# design.net
KiCad netlist of a schematic drawn in Altium Designer
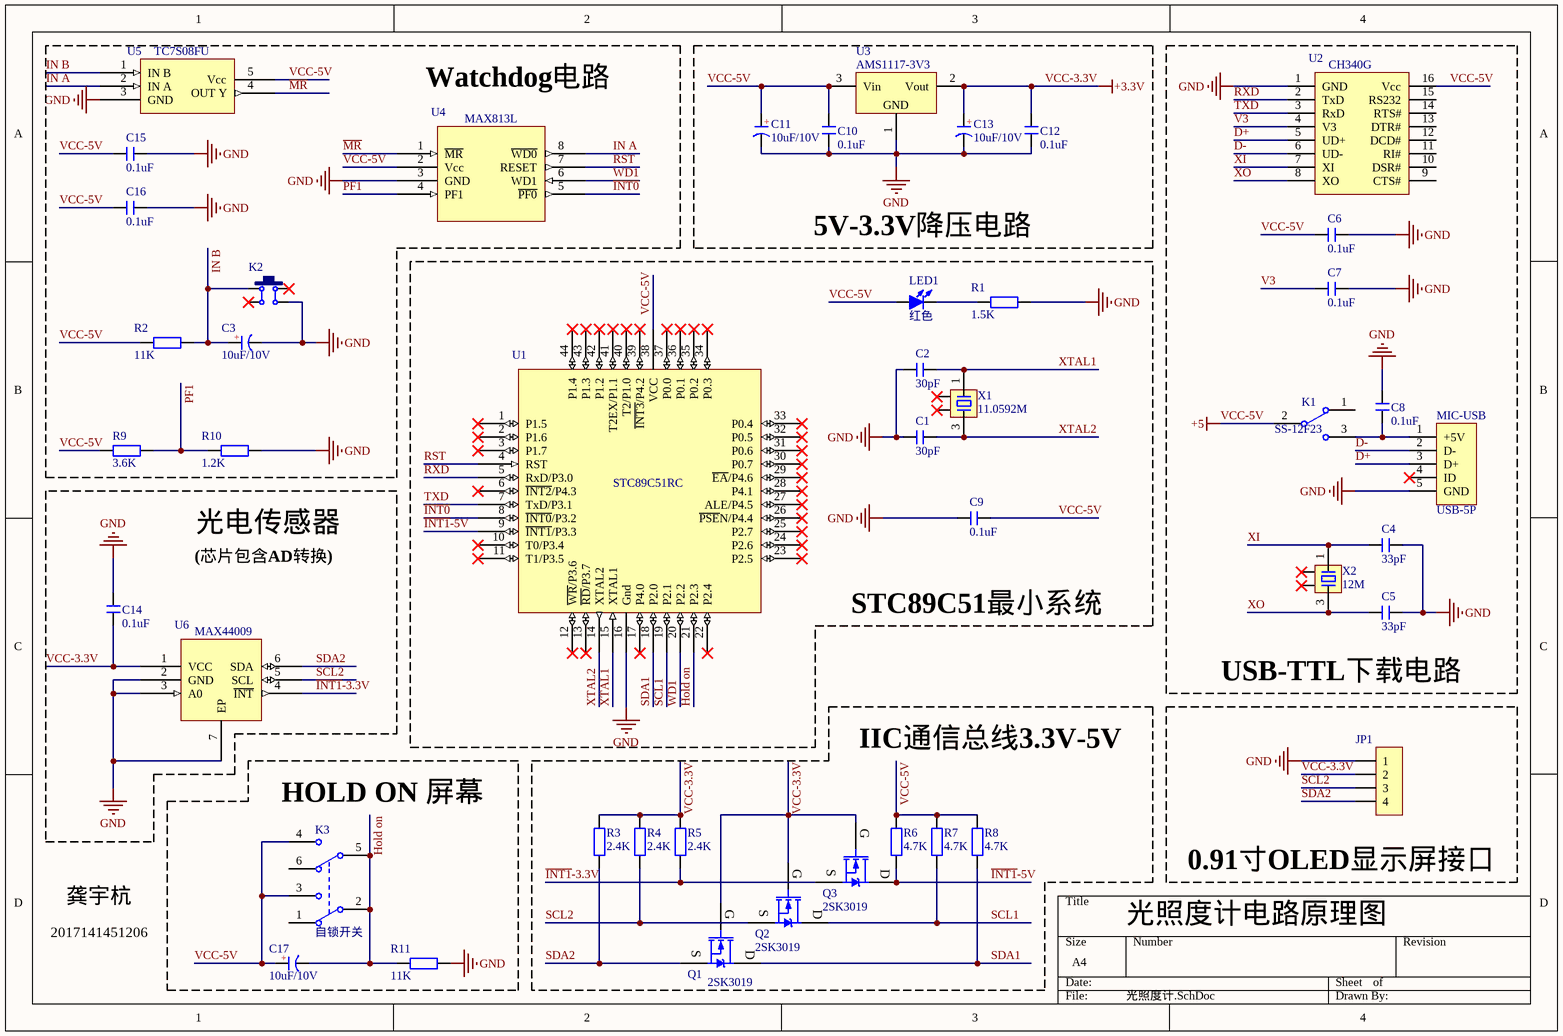
[diagram p0: 光照度计.SchDoc]

(export (version "E")
  (design (tool "Eeschema 10.0.6"))
  (components
    (comp (ref "C1")
      (value "30pF")
      (footprint "C 0805_L")
      (description "贴片电容")
      (libsource (lib "*") (part "C"))
    )
    (comp (ref "C2")
      (value "30pF")
      (footprint "C 0805_L")
      (description "贴片电容")
      (libsource (lib "*") (part "C"))
    )
    (comp (ref "C3")
      (value "10uF/10V")
      (footprint "CM A(3*5.4)")
      (description "贴片电解电容")
      (fields (field (name "版权归属") "封装库来自淘宝 ID：黄晶宝石"))
      (libsource (lib "") (part "CE_SMD_1"))
    )
    (comp (ref "C4")
      (value "33pF")
      (footprint "C 0805_L")
      (description "贴片电容")
      (libsource (lib "*") (part "C"))
    )
    (comp (ref "C5")
      (value "33pF")
      (footprint "C 0805_L")
      (description "贴片电容")
      (libsource (lib "*") (part "C"))
    )
    (comp (ref "C6")
      (value "0.1uF")
      (footprint "C 0805_L")
      (description "贴片电容")
      (libsource (lib "*") (part "C"))
    )
    (comp (ref "C7")
      (value "0.1uF")
      (footprint "C 0805_L")
      (description "贴片电容")
      (libsource (lib "*") (part "C"))
    )
    (comp (ref "C8")
      (value "0.1uF")
      (footprint "C 0805_L")
      (description "贴片电容")
      (libsource (lib "*") (part "C"))
    )
    (comp (ref "C9")
      (value "0.1uF")
      (footprint "C 0805_L")
      (description "贴片电容")
      (libsource (lib "*") (part "C"))
    )
    (comp (ref "C10")
      (value "0.1uF")
      (footprint "C 0805_L")
      (description "贴片电容")
      (libsource (lib "*") (part "C"))
    )
    (comp (ref "C11")
      (value "10uF/10V")
      (footprint "CM A(3*5.4)")
      (description "贴片电解电容")
      (fields (field (name "版权归属") "封装库来自淘宝 ID：黄晶宝石"))
      (libsource (lib "*") (part "CE_SMD"))
    )
    (comp (ref "C12")
      (value "0.1uF")
      (footprint "C 0805_L")
      (description "贴片电容")
      (libsource (lib "*") (part "C"))
    )
    (comp (ref "C13")
      (value "10uF/10V")
      (footprint "CM A(3*5.4)")
      (description "贴片电解电容")
      (fields (field (name "版权归属") "封装库来自淘宝 ID：黄晶宝石"))
      (libsource (lib "*") (part "CE_SMD"))
    )
    (comp (ref "C14")
      (value "0.1uF")
      (footprint "C 0805_L")
      (description "贴片电容")
      (libsource (lib "*") (part "C"))
    )
    (comp (ref "C15")
      (value "0.1uF")
      (footprint "C 0805_L")
      (description "贴片电容")
      (libsource (lib "*") (part "C"))
    )
    (comp (ref "C16")
      (value "0.1uF")
      (footprint "C 0805_L")
      (description "贴片电容")
      (libsource (lib "*") (part "C"))
    )
    (comp (ref "C17")
      (value "10uF/10V")
      (footprint "CM A(3*5.4)")
      (description "贴片电解电容")
      (fields (field (name "版权归属") "封装库来自淘宝 ID：黄晶宝石"))
      (libsource (lib "") (part "CE_SMD_1"))
    )
    (comp (ref "JP1")
      (value "HDR-1X4")
      (footprint "HDR2.54-M-LI-4P")
      (description "4P接插件")
      (fields (field (name "版权归属") "封装库来自淘宝 ID：黄晶宝石"))
      (libsource (lib "*") (part "Header 4"))
    )
    (comp (ref "K1")
      (value "SS-12F23")
      (footprint "MSK-12C01-07")
      (description "1路波动开关")
      (fields (field (name "版权归属") "封装库来自淘宝 ID：黄晶宝石"))
      (libsource (lib "*") (part "SSW-1P"))
    )
    (comp (ref "K2")
      (value "6x6x5")
      (footprint "TSW SMD-6*6*4.3")
      (description "贴片6x6轻触开关")
      (fields (field (name "版权归属") "封装库来自淘宝 ID：黄晶宝石"))
      (libsource (lib "*") (part "TSW SMD-6x6"))
    )
    (comp (ref "K3")
      (value "自锁开关")
      (footprint "KFT DIP-7X7")
      (description "7*7自锁开关")
      (fields (field (name "版权归属") "封装库来自淘宝 ID：黄晶宝石"))
      (libsource (lib "*") (part "KET 7X7"))
    )
    (comp (ref "LED1")
      (value "红色")
      (footprint "LED 0805G")
      (description "贴片LED")
      (fields (field (name "版权归属") "封装库来自淘宝 ID：黄晶宝石"))
      (libsource (lib "*") (part "LED-SMD"))
    )
    (comp (ref "MIC-USB")
      (value "USB-5P")
      (footprint "USB-MICRO_A")
      (description "微型USB母座")
      (libsource (lib "*") (part "USB-5P"))
    )
    (comp (ref "Q1")
      (value "2SK3019")
      (footprint "SOT523")
      (description "N沟场效应管")
      (libsource (lib "*") (part "2SK3019"))
    )
    (comp (ref "Q2")
      (value "2SK3019")
      (footprint "SOT523")
      (description "N沟场效应管")
      (libsource (lib "*") (part "2SK3019"))
    )
    (comp (ref "Q3")
      (value "2SK3019")
      (footprint "SOT523")
      (description "N沟场效应管")
      (libsource (lib "*") (part "2SK3019"))
    )
    (comp (ref "R1")
      (value "1.5K")
      (footprint "R 0805_L")
      (description "贴片电阻")
      (fields (field (name "版权归属") "来自淘宝 ID：黄晶宝石"))
      (libsource (lib "*") (part "R"))
    )
    (comp (ref "R2")
      (value "11K")
      (footprint "R 0805_L")
      (description "贴片电阻")
      (fields (field (name "版权归属") "来自淘宝 ID：黄晶宝石"))
      (libsource (lib "*") (part "R"))
    )
    (comp (ref "R3")
      (value "2.4K")
      (footprint "R 0805_L")
      (description "贴片电阻")
      (fields (field (name "版权归属") "来自淘宝 ID：黄晶宝石"))
      (libsource (lib "*") (part "R"))
    )
    (comp (ref "R4")
      (value "2.4K")
      (footprint "R 0805_L")
      (description "贴片电阻")
      (fields (field (name "版权归属") "来自淘宝 ID：黄晶宝石"))
      (libsource (lib "*") (part "R"))
    )
    (comp (ref "R5")
      (value "2.4K")
      (footprint "R 0805_L")
      (description "贴片电阻")
      (fields (field (name "版权归属") "来自淘宝 ID：黄晶宝石"))
      (libsource (lib "*") (part "R"))
    )
    (comp (ref "R6")
      (value "4.7K")
      (footprint "R 0805_L")
      (description "贴片电阻")
      (fields (field (name "版权归属") "来自淘宝 ID：黄晶宝石"))
      (libsource (lib "*") (part "R"))
    )
    (comp (ref "R7")
      (value "4.7K")
      (footprint "R 0805_L")
      (description "贴片电阻")
      (fields (field (name "版权归属") "来自淘宝 ID：黄晶宝石"))
      (libsource (lib "*") (part "R"))
    )
    (comp (ref "R8")
      (value "4.7K")
      (footprint "R 0805_L")
      (description "贴片电阻")
      (fields (field (name "版权归属") "来自淘宝 ID：黄晶宝石"))
      (libsource (lib "*") (part "R"))
    )
    (comp (ref "R9")
      (value "3.6K")
      (footprint "R 0805_L")
      (description "贴片电阻")
      (fields (field (name "版权归属") "来自淘宝 ID：黄晶宝石"))
      (libsource (lib "*") (part "R"))
    )
    (comp (ref "R10")
      (value "1.2K")
      (footprint "R 0805_L")
      (description "贴片电阻")
      (fields (field (name "版权归属") "来自淘宝 ID：黄晶宝石"))
      (libsource (lib "*") (part "R"))
    )
    (comp (ref "R11")
      (value "11K")
      (footprint "R 0805_L")
      (description "贴片电阻")
      (fields (field (name "版权归属") "来自淘宝 ID：黄晶宝石"))
      (libsource (lib "*") (part "R"))
    )
    (comp (ref "U1")
      (value "STC89C51RC")
      (footprint "LQFP44 10X10_N")
      (description "STC单片机贴片")
      (libsource (lib "*") (part "STC89C51RC-44pin"))
    )
    (comp (ref "U2")
      (value "CH340G")
      (footprint "SOP16_N")
      (description "串口转USB")
      (fields (field (name "版权归属") "封装库来自淘宝 ID：黄晶宝石"))
      (libsource (lib "*") (part "CH340G"))
    )
    (comp (ref "U3")
      (value "AMS1117-3V3")
      (footprint "SOT223_N")
      (description "三端稳压芯片")
      (libsource (lib "02模块IC器件库") (part "AMS1117"))
    )
    (comp (ref "U4")
      (value "MAX813L")
      (footprint "SOP8-N-MAX813L")
      (description "电源监控芯片（看门狗）")
      (libsource (lib "*") (part "MAX813L"))
    )
    (comp (ref "U5")
      (value "TC7S08FU")
      (footprint "TSOP65P210X100-5M")
      (description "2输入与门（一个）")
      (libsource (lib "*") (part "TC7S08FU-2输入与门"))
    )
    (comp (ref "U6")
      (value "MAX44009")
      (footprint "QFN65P200X200X65_HS-7N")
      (description "光照度传感器")
      (libsource (lib "*") (part "MAX44009"))
    )
    (comp (ref "X1")
      (value "11.0592M")
      (footprint "OSC 3225-4P")
      (description "4脚无源晶振")
      (fields (field (name "版权归属") "封装库来自淘宝卖家 ID：黄晶宝石"))
      (libsource (lib "*") (part "XTAL-4P"))
    )
    (comp (ref "X2")
      (value "12M")
      (footprint "OSC 3225-4P")
      (description "4脚无源晶振")
      (fields (field (name "版权归属") "封装库来自淘宝卖家 ID：黄晶宝石"))
      (libsource (lib "*") (part "XTAL-4P"))
    )
  )
  (nets
    (net (code "1") (name "+3.3V") (class "Default")
      (node (ref "C12") (pin "2") (pinfunction "2_2") (pintype "passive"))
      (node (ref "C13") (pin "1") (pinfunction "A_1") (pintype "passive"))
      (node (ref "C14") (pin "2") (pinfunction "2_2") (pintype "passive"))
      (node (ref "JP1") (pin "2") (pinfunction "2_2") (pintype "passive"))
      (node (ref "Q1") (pin "1") (pinfunction "G_1") (pintype "passive"))
      (node (ref "Q2") (pin "1") (pinfunction "G_1") (pintype "passive"))
      (node (ref "Q3") (pin "1") (pinfunction "G_1") (pintype "passive"))
      (node (ref "R3") (pin "2") (pinfunction "2_2") (pintype "passive"))
      (node (ref "R4") (pin "2") (pinfunction "2_2") (pintype "passive"))
      (node (ref "R5") (pin "2") (pinfunction "2_2") (pintype "passive"))
      (node (ref "U3") (pin "2") (pinfunction "Vout_2") (pintype "passive"))
      (node (ref "U6") (pin "1") (pinfunction "VCC_1") (pintype "power_in"))
    )
    (net (code "2") (name "+5") (class "Default")
      (node (ref "C10") (pin "2") (pinfunction "2_2") (pintype "passive"))
      (node (ref "C11") (pin "1") (pinfunction "A_1") (pintype "passive"))
      (node (ref "C15") (pin "2") (pinfunction "2_2") (pintype "passive"))
      (node (ref "C16") (pin "2") (pinfunction "2_2") (pintype "passive"))
      (node (ref "C17") (pin "1") (pinfunction "A_1") (pintype "passive"))
      (node (ref "C6") (pin "2") (pinfunction "2_2") (pintype "passive"))
      (node (ref "C9") (pin "2") (pinfunction "2_2") (pintype "passive"))
      (node (ref "K1") (pin "2") (pinfunction "2_2") (pintype "passive"))
      (node (ref "K3") (pin "3") (pinfunction "NO1_3") (pintype "passive"))
      (node (ref "K3") (pin "4") (pinfunction "NO2_4") (pintype "passive"))
      (node (ref "LED1") (pin "1") (pinfunction "A_1") (pintype "passive"))
      (node (ref "R2") (pin "1") (pinfunction "1_1") (pintype "passive"))
      (node (ref "R6") (pin "2") (pinfunction "2_2") (pintype "passive"))
      (node (ref "R7") (pin "2") (pinfunction "2_2") (pintype "passive"))
      (node (ref "R8") (pin "2") (pinfunction "2_2") (pintype "passive"))
      (node (ref "R9") (pin "2") (pinfunction "2_2") (pintype "passive"))
      (node (ref "U1") (pin "38") (pinfunction "VCC_38") (pintype "power_in"))
      (node (ref "U2") (pin "16") (pinfunction "Vcc_16") (pintype "passive"))
      (node (ref "U3") (pin "3") (pinfunction "Vin_3") (pintype "passive"))
      (node (ref "U4") (pin "2") (pinfunction "Vcc_2") (pintype "power_in"))
      (node (ref "U5") (pin "5") (pinfunction "Vcc_5") (pintype "power_in"))
    )
    (net (code "3") (name "/D+") (class "Default")
      (node (ref "MIC-USB") (pin "3") (pinfunction "D+_3") (pintype "passive"))
      (node (ref "U2") (pin "5") (pinfunction "UD+_5") (pintype "passive"))
    )
    (net (code "4") (name "/D-") (class "Default")
      (node (ref "MIC-USB") (pin "2") (pinfunction "D-_2") (pintype "passive"))
      (node (ref "U2") (pin "6") (pinfunction "UD-_6") (pintype "passive"))
    )
    (net (code "5") (name "/Hold on") (class "Default")
      (node (ref "C17") (pin "2") (pinfunction "K_2") (pintype "passive"))
      (node (ref "K3") (pin "2") (pinfunction "COM2_2") (pintype "passive"))
      (node (ref "K3") (pin "5") (pinfunction "COM2_5") (pintype "passive"))
      (node (ref "R11") (pin "1") (pinfunction "1_1") (pintype "passive"))
      (node (ref "U1") (pin "21") (pinfunction "P2.3_21") (pintype "bidirectional"))
    )
    (net (code "6") (name "/IN A") (class "Default")
      (node (ref "U4") (pin "8") (pinfunction "~{WD0}_8") (pintype "output"))
      (node (ref "U5") (pin "2") (pinfunction "IN_A_2") (pintype "input"))
    )
    (net (code "7") (name "/IN B") (class "Default")
      (node (ref "C3") (pin "1") (pinfunction "A_1") (pintype "passive"))
      (node (ref "K2") (pin "1") (pinfunction "1_1") (pintype "passive"))
      (node (ref "R2") (pin "2") (pinfunction "2_2") (pintype "passive"))
      (node (ref "U5") (pin "1") (pinfunction "IN_B_1") (pintype "input"))
    )
    (net (code "8") (name "/PF1") (class "Default")
      (node (ref "R10") (pin "1") (pinfunction "1_1") (pintype "passive"))
      (node (ref "R9") (pin "1") (pinfunction "1_1") (pintype "passive"))
      (node (ref "U4") (pin "4") (pinfunction "PF1_4") (pintype "input"))
    )
    (net (code "9") (name "/RST") (class "Default")
      (node (ref "U1") (pin "4") (pinfunction "RST_4") (pintype "input"))
      (node (ref "U4") (pin "7") (pinfunction "RESET_7") (pintype "output"))
    )
    (net (code "10") (name "/RXD") (class "Default")
      (node (ref "U1") (pin "5") (pinfunction "RxD/P3.0_5") (pintype "bidirectional"))
      (node (ref "U2") (pin "2") (pinfunction "TxD_2") (pintype "passive"))
    )
    (net (code "11") (name "/SCL1") (class "Default")
      (node (ref "Q2") (pin "2") (pinfunction "D_2") (pintype "passive"))
      (node (ref "R7") (pin "1") (pinfunction "1_1") (pintype "passive"))
      (node (ref "U1") (pin "19") (pinfunction "P2.1_19") (pintype "bidirectional"))
    )
    (net (code "12") (name "/SCL2") (class "Default")
      (node (ref "JP1") (pin "3") (pinfunction "3_3") (pintype "passive"))
      (node (ref "Q2") (pin "3") (pinfunction "S_3") (pintype "passive"))
      (node (ref "R4") (pin "1") (pinfunction "1_1") (pintype "passive"))
      (node (ref "U6") (pin "5") (pinfunction "SCL_5") (pintype "bidirectional"))
    )
    (net (code "13") (name "/SDA1") (class "Default")
      (node (ref "Q1") (pin "2") (pinfunction "D_2") (pintype "passive"))
      (node (ref "R8") (pin "1") (pinfunction "1_1") (pintype "passive"))
      (node (ref "U1") (pin "18") (pinfunction "P2.0_18") (pintype "bidirectional"))
    )
    (net (code "14") (name "/SDA2") (class "Default")
      (node (ref "JP1") (pin "4") (pinfunction "4_4") (pintype "passive"))
      (node (ref "Q1") (pin "3") (pinfunction "S_3") (pintype "passive"))
      (node (ref "R3") (pin "1") (pinfunction "1_1") (pintype "passive"))
      (node (ref "U6") (pin "6") (pinfunction "SDA_6") (pintype "bidirectional"))
    )
    (net (code "15") (name "/TXD") (class "Default")
      (node (ref "U1") (pin "7") (pinfunction "TxD/P3.1_7") (pintype "bidirectional"))
      (node (ref "U2") (pin "3") (pinfunction "RxD_3") (pintype "passive"))
    )
    (net (code "16") (name "/V3") (class "Default")
      (node (ref "C7") (pin "2") (pinfunction "2_2") (pintype "passive"))
      (node (ref "U2") (pin "4") (pinfunction "V3_4") (pintype "passive"))
    )
    (net (code "17") (name "/WD1") (class "Default")
      (node (ref "U1") (pin "20") (pinfunction "P2.2_20") (pintype "bidirectional"))
      (node (ref "U4") (pin "6") (pinfunction "WD1_6") (pintype "input"))
    )
    (net (code "18") (name "/XI") (class "Default")
      (node (ref "C4") (pin "2") (pinfunction "2_2") (pintype "passive"))
      (node (ref "U2") (pin "7") (pinfunction "XI_7") (pintype "passive"))
      (node (ref "X2") (pin "1") (pinfunction "1_1") (pintype "passive"))
    )
    (net (code "19") (name "/XO") (class "Default")
      (node (ref "C5") (pin "2") (pinfunction "2_2") (pintype "passive"))
      (node (ref "U2") (pin "8") (pinfunction "XO_8") (pintype "passive"))
      (node (ref "X2") (pin "3") (pinfunction "3_3") (pintype "passive"))
    )
    (net (code "20") (name "/XTAL1") (class "Default")
      (node (ref "C2") (pin "1") (pinfunction "1_1") (pintype "passive"))
      (node (ref "U1") (pin "15") (pinfunction "XTAL1_15") (pintype "input"))
      (node (ref "X1") (pin "1") (pinfunction "1_1") (pintype "passive"))
    )
    (net (code "21") (name "/XTAL2") (class "Default")
      (node (ref "C1") (pin "2") (pinfunction "2_2") (pintype "passive"))
      (node (ref "U1") (pin "14") (pinfunction "XTAL2_14") (pintype "output"))
      (node (ref "X1") (pin "3") (pinfunction "3_3") (pintype "passive"))
    )
    (net (code "22") (name "/~{INT0}") (class "Default")
      (node (ref "U1") (pin "8") (pinfunction "~{INT0}/P3.2_8") (pintype "bidirectional"))
      (node (ref "U4") (pin "5") (pinfunction "~{PF0}_5") (pintype "output"))
    )
    (net (code "23") (name "/~{INT1}-3.3V") (class "Default")
      (node (ref "Q3") (pin "3") (pinfunction "S_3") (pintype "passive"))
      (node (ref "R5") (pin "1") (pinfunction "1_1") (pintype "passive"))
      (node (ref "U6") (pin "4") (pinfunction "~{INT}_4") (pintype "output"))
    )
    (net (code "24") (name "/~{INT1}-5V") (class "Default")
      (node (ref "Q3") (pin "2") (pinfunction "D_2") (pintype "passive"))
      (node (ref "R6") (pin "1") (pinfunction "1_1") (pintype "passive"))
      (node (ref "U1") (pin "9") (pinfunction "~{INT1}/P3.3_9") (pintype "bidirectional"))
    )
    (net (code "25") (name "/~{MR}") (class "Default")
      (node (ref "U4") (pin "1") (pinfunction "~{MR}_1") (pintype "input"))
      (node (ref "U5") (pin "4") (pinfunction "OUT_Y_4") (pintype "output"))
    )
    (net (code "26") (name "GND") (class "Default")
      (node (ref "C1") (pin "1") (pinfunction "1_1") (pintype "passive"))
      (node (ref "C10") (pin "1") (pinfunction "1_1") (pintype "passive"))
      (node (ref "C11") (pin "2") (pinfunction "K_2") (pintype "passive"))
      (node (ref "C12") (pin "1") (pinfunction "1_1") (pintype "passive"))
      (node (ref "C13") (pin "2") (pinfunction "K_2") (pintype "passive"))
      (node (ref "C14") (pin "1") (pinfunction "1_1") (pintype "passive"))
      (node (ref "C15") (pin "1") (pinfunction "1_1") (pintype "passive"))
      (node (ref "C16") (pin "1") (pinfunction "1_1") (pintype "passive"))
      (node (ref "C2") (pin "2") (pinfunction "2_2") (pintype "passive"))
      (node (ref "C3") (pin "2") (pinfunction "K_2") (pintype "passive"))
      (node (ref "C4") (pin "1") (pinfunction "1_1") (pintype "passive"))
      (node (ref "C5") (pin "1") (pinfunction "1_1") (pintype "passive"))
      (node (ref "C6") (pin "1") (pinfunction "1_1") (pintype "passive"))
      (node (ref "C7") (pin "1") (pinfunction "1_1") (pintype "passive"))
      (node (ref "C8") (pin "1") (pinfunction "1_1") (pintype "passive"))
      (node (ref "C9") (pin "1") (pinfunction "1_1") (pintype "passive"))
      (node (ref "JP1") (pin "1") (pinfunction "1_1") (pintype "passive"))
      (node (ref "K2") (pin "3") (pinfunction "3_3") (pintype "passive"))
      (node (ref "MIC-USB") (pin "5") (pinfunction "GND_5") (pintype "passive"))
      (node (ref "R1") (pin "2") (pinfunction "2_2") (pintype "passive"))
      (node (ref "R10") (pin "2") (pinfunction "2_2") (pintype "passive"))
      (node (ref "R11") (pin "2") (pinfunction "2_2") (pintype "passive"))
      (node (ref "U1") (pin "16") (pinfunction "Gnd_16") (pintype "power_in"))
      (node (ref "U2") (pin "1") (pinfunction "GND_1") (pintype "passive"))
      (node (ref "U3") (pin "1") (pinfunction "GND_1") (pintype "passive"))
      (node (ref "U4") (pin "3") (pinfunction "GND_3") (pintype "power_in"))
      (node (ref "U5") (pin "3") (pinfunction "GND_3") (pintype "power_in"))
      (node (ref "U6") (pin "2") (pinfunction "GND_2") (pintype "power_in"))
      (node (ref "U6") (pin "3") (pinfunction "A0_3") (pintype "input"))
      (node (ref "U6") (pin "7") (pinfunction "EP_7") (pintype "power_in"))
    )
    (net (code "27") (name "Net-(LED1-K)") (class "Default")
      (node (ref "LED1") (pin "2") (pinfunction "K_2") (pintype "passive"))
      (node (ref "R1") (pin "1") (pinfunction "1_1") (pintype "passive"))
    )
    (net (code "28") (name "Net-(MIC-USB-+5V)") (class "Default")
      (node (ref "C8") (pin "2") (pinfunction "2_2") (pintype "passive"))
      (node (ref "K1") (pin "3") (pinfunction "3_3") (pintype "passive"))
      (node (ref "MIC-USB") (pin "1") (pinfunction "+5V_1") (pintype "passive"))
    )
    (net (code "29") (name "unconnected-(K1-Pad1)") (class "Default")
      (node (ref "K1") (pin "1") (pinfunction "1_1") (pintype "passive"))
    )
    (net (code "30") (name "unconnected-(K2-Pad2)") (class "Default")
      (node (ref "K2") (pin "2") (pinfunction "2_2") (pintype "passive+no_connect"))
    )
    (net (code "31") (name "unconnected-(K2-Pad4)") (class "Default")
      (node (ref "K2") (pin "4") (pinfunction "4_4") (pintype "passive+no_connect"))
    )
    (net (code "32") (name "unconnected-(K3-NC1-Pad1)") (class "Default")
      (node (ref "K3") (pin "1") (pinfunction "NC1_1") (pintype "passive"))
    )
    (net (code "33") (name "unconnected-(K3-NC2-Pad6)") (class "Default")
      (node (ref "K3") (pin "6") (pinfunction "NC2_6") (pintype "passive"))
    )
    (net (code "34") (name "unconnected-(MIC-USB-ID-Pad4)") (class "Default")
      (node (ref "MIC-USB") (pin "4") (pinfunction "ID_4") (pintype "passive+no_connect"))
    )
    (net (code "35") (name "unconnected-(U1-ALE{slash}P4.5-Pad27)") (class "Default")
      (node (ref "U1") (pin "27") (pinfunction "ALE/P4.5_27") (pintype "bidirectional+no_connect"))
    )
    (net (code "36") (name "unconnected-(U1-P0.0-Pad37)") (class "Default")
      (node (ref "U1") (pin "37") (pinfunction "P0.0_37") (pintype "bidirectional+no_connect"))
    )
    (net (code "37") (name "unconnected-(U1-P0.1-Pad36)") (class "Default")
      (node (ref "U1") (pin "36") (pinfunction "P0.1_36") (pintype "bidirectional+no_connect"))
    )
    (net (code "38") (name "unconnected-(U1-P0.2-Pad35)") (class "Default")
      (node (ref "U1") (pin "35") (pinfunction "P0.2_35") (pintype "bidirectional+no_connect"))
    )
    (net (code "39") (name "unconnected-(U1-P0.3-Pad34)") (class "Default")
      (node (ref "U1") (pin "34") (pinfunction "P0.3_34") (pintype "bidirectional+no_connect"))
    )
    (net (code "40") (name "unconnected-(U1-P0.4-Pad33)") (class "Default")
      (node (ref "U1") (pin "33") (pinfunction "P0.4_33") (pintype "bidirectional+no_connect"))
    )
    (net (code "41") (name "unconnected-(U1-P0.5-Pad32)") (class "Default")
      (node (ref "U1") (pin "32") (pinfunction "P0.5_32") (pintype "bidirectional+no_connect"))
    )
    (net (code "42") (name "unconnected-(U1-P0.6-Pad31)") (class "Default")
      (node (ref "U1") (pin "31") (pinfunction "P0.6_31") (pintype "bidirectional+no_connect"))
    )
    (net (code "43") (name "unconnected-(U1-P0.7-Pad30)") (class "Default")
      (node (ref "U1") (pin "30") (pinfunction "P0.7_30") (pintype "bidirectional+no_connect"))
    )
    (net (code "44") (name "unconnected-(U1-P1.2-Pad42)") (class "Default")
      (node (ref "U1") (pin "42") (pinfunction "P1.2_42") (pintype "bidirectional+no_connect"))
    )
    (net (code "45") (name "unconnected-(U1-P1.3-Pad43)") (class "Default")
      (node (ref "U1") (pin "43") (pinfunction "P1.3_43") (pintype "bidirectional+no_connect"))
    )
    (net (code "46") (name "unconnected-(U1-P1.4-Pad44)") (class "Default")
      (node (ref "U1") (pin "44") (pinfunction "P1.4_44") (pintype "bidirectional+no_connect"))
    )
    (net (code "47") (name "unconnected-(U1-P1.5-Pad1)") (class "Default")
      (node (ref "U1") (pin "1") (pinfunction "P1.5_1") (pintype "bidirectional+no_connect"))
    )
    (net (code "48") (name "unconnected-(U1-P1.6-Pad2)") (class "Default")
      (node (ref "U1") (pin "2") (pinfunction "P1.6_2") (pintype "bidirectional+no_connect"))
    )
    (net (code "49") (name "unconnected-(U1-P1.7-Pad3)") (class "Default")
      (node (ref "U1") (pin "3") (pinfunction "P1.7_3") (pintype "bidirectional+no_connect"))
    )
    (net (code "50") (name "unconnected-(U1-P2.4-Pad22)") (class "Default")
      (node (ref "U1") (pin "22") (pinfunction "P2.4_22") (pintype "bidirectional+no_connect"))
    )
    (net (code "51") (name "unconnected-(U1-P2.5-Pad23)") (class "Default")
      (node (ref "U1") (pin "23") (pinfunction "P2.5_23") (pintype "bidirectional+no_connect"))
    )
    (net (code "52") (name "unconnected-(U1-P2.6-Pad24)") (class "Default")
      (node (ref "U1") (pin "24") (pinfunction "P2.6_24") (pintype "bidirectional+no_connect"))
    )
    (net (code "53") (name "unconnected-(U1-P2.7-Pad25)") (class "Default")
      (node (ref "U1") (pin "25") (pinfunction "P2.7_25") (pintype "bidirectional+no_connect"))
    )
    (net (code "54") (name "unconnected-(U1-P4.0-Pad17)") (class "Default")
      (node (ref "U1") (pin "17") (pinfunction "P4.0_17") (pintype "bidirectional+no_connect"))
    )
    (net (code "55") (name "unconnected-(U1-P4.1-Pad28)") (class "Default")
      (node (ref "U1") (pin "28") (pinfunction "P4.1_28") (pintype "bidirectional+no_connect"))
    )
    (net (code "56") (name "unconnected-(U1-T0{slash}P3.4-Pad10)") (class "Default")
      (node (ref "U1") (pin "10") (pinfunction "T0/P3.4_10") (pintype "bidirectional+no_connect"))
    )
    (net (code "57") (name "unconnected-(U1-T1{slash}P3.5-Pad11)") (class "Default")
      (node (ref "U1") (pin "11") (pinfunction "T1/P3.5_11") (pintype "bidirectional+no_connect"))
    )
    (net (code "58") (name "unconnected-(U1-T2EX{slash}P1.1-Pad41)") (class "Default")
      (node (ref "U1") (pin "41") (pinfunction "T2EX/P1.1_41") (pintype "bidirectional+no_connect"))
    )
    (net (code "59") (name "unconnected-(U1-T2{slash}P1.0-Pad40)") (class "Default")
      (node (ref "U1") (pin "40") (pinfunction "T2/P1.0_40") (pintype "bidirectional+no_connect"))
    )
    (net (code "60") (name "unconnected-(U1-~{EA}{slash}P4.6-Pad29)") (class "Default")
      (node (ref "U1") (pin "29") (pinfunction "~{EA}/P4.6_29") (pintype "bidirectional+no_connect"))
    )
    (net (code "61") (name "unconnected-(U1-~{INT2}{slash}P4.3-Pad6)") (class "Default")
      (node (ref "U1") (pin "6") (pinfunction "~{INT2}/P4.3_6") (pintype "bidirectional+no_connect"))
    )
    (net (code "62") (name "unconnected-(U1-~{INT3}{slash}P4.2-Pad39)") (class "Default")
      (node (ref "U1") (pin "39") (pinfunction "~{INT3}/P4.2_39") (pintype "bidirectional+no_connect"))
    )
    (net (code "63") (name "unconnected-(U1-~{PSE}N{slash}P4.4-Pad26)") (class "Default")
      (node (ref "U1") (pin "26") (pinfunction "~{PSE}N/P4.4_26") (pintype "bidirectional+no_connect"))
    )
    (net (code "64") (name "unconnected-(U1-~{RD}{slash}P3.7-Pad13)") (class "Default")
      (node (ref "U1") (pin "13") (pinfunction "~{RD}/P3.7_13") (pintype "bidirectional+no_connect"))
    )
    (net (code "65") (name "unconnected-(U1-~{WR}{slash}P3.6-Pad12)") (class "Default")
      (node (ref "U1") (pin "12") (pinfunction "~{WR}/P3.6_12") (pintype "bidirectional+no_connect"))
    )
    (net (code "66") (name "unconnected-(U2-CTS#-Pad9)") (class "Default")
      (node (ref "U2") (pin "9") (pinfunction "CTS#_9") (pintype "passive"))
    )
    (net (code "67") (name "unconnected-(U2-DCD#-Pad12)") (class "Default")
      (node (ref "U2") (pin "12") (pinfunction "DCD#_12") (pintype "passive"))
    )
    (net (code "68") (name "unconnected-(U2-DSR#-Pad10)") (class "Default")
      (node (ref "U2") (pin "10") (pinfunction "DSR#_10") (pintype "passive"))
    )
    (net (code "69") (name "unconnected-(U2-DTR#-Pad13)") (class "Default")
      (node (ref "U2") (pin "13") (pinfunction "DTR#_13") (pintype "passive"))
    )
    (net (code "70") (name "unconnected-(U2-RI#-Pad11)") (class "Default")
      (node (ref "U2") (pin "11") (pinfunction "RI#_11") (pintype "passive"))
    )
    (net (code "71") (name "unconnected-(U2-RS232-Pad15)") (class "Default")
      (node (ref "U2") (pin "15") (pinfunction "RS232_15") (pintype "passive"))
    )
    (net (code "72") (name "unconnected-(U2-RTS#-Pad14)") (class "Default")
      (node (ref "U2") (pin "14") (pinfunction "RTS#_14") (pintype "passive"))
    )
    (net (code "73") (name "unconnected-(X1-Pad2)") (class "Default")
      (node (ref "X1") (pin "2") (pinfunction "2_2") (pintype "passive+no_connect"))
    )
    (net (code "74") (name "unconnected-(X1-Pad4)") (class "Default")
      (node (ref "X1") (pin "4") (pinfunction "4_4") (pintype "passive+no_connect"))
    )
    (net (code "75") (name "unconnected-(X2-Pad2)") (class "Default")
      (node (ref "X2") (pin "2") (pinfunction "2_2") (pintype "passive+no_connect"))
    )
    (net (code "76") (name "unconnected-(X2-Pad4)") (class "Default")
      (node (ref "X2") (pin "4") (pinfunction "4_4") (pintype "passive+no_connect"))
    )
  )
)
